# controller.net
KiCad netlist of a schematic drawn in EAGLE
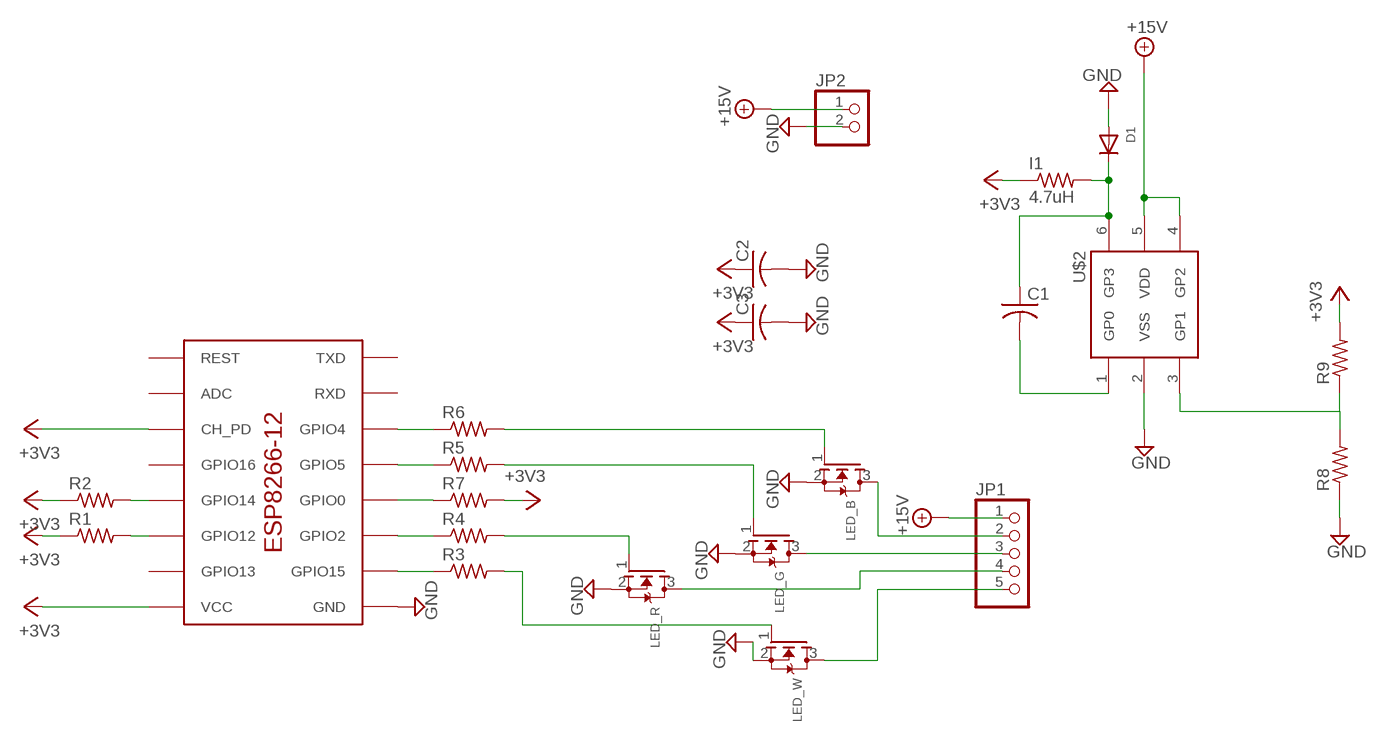
[diagram p0: schematic, sheet 1]

(export (version "E")
  (design (tool "Eeschema 10.0.6"))
  (components
    (comp (ref "C1")
      (value "C-USC0805")
      (footprint "eagle-import:C0805")
      (libsource (lib "eagle-import") (part "C-USC0805"))
    )
    (comp (ref "C2")
      (value "C-USC0805")
      (footprint "eagle-import:C0805")
      (libsource (lib "eagle-import") (part "C-USC0805"))
    )
    (comp (ref "C3")
      (value "C-USC0805")
      (footprint "eagle-import:C0805")
      (libsource (lib "eagle-import") (part "C-USC0805"))
    )
    (comp (ref "D1")
      (value "DIODESOT23_REFLOW")
      (footprint "eagle-import:SOT23-R")
      (libsource (lib "eagle-import") (part "DIODESOT23_REFLOW"))
    )
    (comp (ref "I1")
      (value "4.7uH")
      (footprint "eagle-import:R0805")
      (libsource (lib "eagle-import") (part "R-US_R0805"))
    )
    (comp (ref "JP1")
      (value "PINHD-1X5")
      (footprint "eagle-import:1X05")
      (libsource (lib "eagle-import") (part "PINHD-1X5"))
    )
    (comp (ref "JP2")
      (value "PINHD-1X2")
      (footprint "eagle-import:1X02")
      (libsource (lib "eagle-import") (part "PINHD-1X2"))
    )
    (comp (ref "LED_B")
      (value "MOSFET-NREFLOW")
      (footprint "eagle-import:SOT23")
      (libsource (lib "eagle-import") (part "MOSFET-NREFLOW"))
    )
    (comp (ref "LED_G")
      (value "MOSFET-NREFLOW")
      (footprint "eagle-import:SOT23")
      (libsource (lib "eagle-import") (part "MOSFET-NREFLOW"))
    )
    (comp (ref "LED_R")
      (value "MOSFET-NREFLOW")
      (footprint "eagle-import:SOT23")
      (libsource (lib "eagle-import") (part "MOSFET-NREFLOW"))
    )
    (comp (ref "LED_W")
      (value "MOSFET-NREFLOW")
      (footprint "eagle-import:SOT23")
      (libsource (lib "eagle-import") (part "MOSFET-NREFLOW"))
    )
    (comp (ref "R1")
      (value "R-US_R0805")
      (footprint "eagle-import:R0805")
      (libsource (lib "eagle-import") (part "R-US_R0805"))
    )
    (comp (ref "R2")
      (value "R-US_R0805")
      (footprint "eagle-import:R0805")
      (libsource (lib "eagle-import") (part "R-US_R0805"))
    )
    (comp (ref "R3")
      (value "R-US_R0805")
      (footprint "eagle-import:R0805")
      (libsource (lib "eagle-import") (part "R-US_R0805"))
    )
    (comp (ref "R4")
      (value "R-US_R0805")
      (footprint "eagle-import:R0805")
      (libsource (lib "eagle-import") (part "R-US_R0805"))
    )
    (comp (ref "R5")
      (value "R-US_R0805")
      (footprint "eagle-import:R0805")
      (libsource (lib "eagle-import") (part "R-US_R0805"))
    )
    (comp (ref "R6")
      (value "R-US_R0805")
      (footprint "eagle-import:R0805")
      (libsource (lib "eagle-import") (part "R-US_R0805"))
    )
    (comp (ref "R7")
      (value "R-US_R0805")
      (footprint "eagle-import:R0805")
      (libsource (lib "eagle-import") (part "R-US_R0805"))
    )
    (comp (ref "R8")
      (value "R-US_R0805")
      (footprint "eagle-import:R0805")
      (libsource (lib "eagle-import") (part "R-US_R0805"))
    )
    (comp (ref "R9")
      (value "R-US_R0805")
      (footprint "eagle-import:R0805")
      (libsource (lib "eagle-import") (part "R-US_R0805"))
    )
    (comp (ref "U$1")
      (value "ESP8266-12")
      (footprint "eagle-import:ESP8266-12")
      (libsource (lib "eagle-import") (part "ESP8266-12"))
    )
    (comp (ref "U$2")
      (value "10F200T")
      (footprint "eagle-import:SOT23-6")
      (libsource (lib "eagle-import") (part "10F200T"))
    )
  )
  (nets
    (net (code "1") (name "+3V3") (class "Default")
      (node (ref "C2") (pin "1") (pinfunction "1_1") (pintype "passive"))
      (node (ref "C3") (pin "1") (pinfunction "1_1") (pintype "passive"))
      (node (ref "I1") (pin "1") (pinfunction "1_1") (pintype "passive"))
      (node (ref "R1") (pin "1") (pinfunction "1_1") (pintype "passive"))
      (node (ref "R2") (pin "1") (pinfunction "1_1") (pintype "passive"))
      (node (ref "R7") (pin "2") (pinfunction "2_2") (pintype "passive"))
      (node (ref "R9") (pin "2") (pinfunction "2_2") (pintype "passive"))
      (node (ref "U$1") (pin "CH_PD") (pinfunction "CH_PD_CH_PD") (pintype "power_in"))
      (node (ref "U$1") (pin "VCC") (pinfunction "VCC_VCC") (pintype "power_in"))
    )
    (net (code "2") (name "+15V") (class "Default")
      (node (ref "JP1") (pin "1") (pinfunction "1_1") (pintype "passive"))
      (node (ref "JP2") (pin "1") (pinfunction "1_1") (pintype "passive"))
      (node (ref "U$2") (pin "4") (pinfunction "GP2_4") (pintype "bidirectional"))
      (node (ref "U$2") (pin "5") (pinfunction "VDD_5") (pintype "power_in"))
    )
    (net (code "3") (name "/ADC") (class "Default")
      (node (ref "U$1") (pin "ADC") (pinfunction "ADC_ADC") (pintype "power_in"))
    )
    (net (code "4") (name "/GPIO13") (class "Default")
      (node (ref "U$1") (pin "GPIO13") (pinfunction "GPIO13_GPIO13") (pintype "power_in"))
    )
    (net (code "5") (name "/GPIO16") (class "Default")
      (node (ref "U$1") (pin "GPIO16") (pinfunction "GPIO16_GPIO16") (pintype "power_in"))
    )
    (net (code "6") (name "/REST") (class "Default")
      (node (ref "U$1") (pin "REST") (pinfunction "REST_REST") (pintype "power_in"))
    )
    (net (code "7") (name "/RXD") (class "Default")
      (node (ref "U$1") (pin "RXD") (pinfunction "RXD_RXD") (pintype "power_in"))
    )
    (net (code "8") (name "/TXD") (class "Default")
      (node (ref "U$1") (pin "TXD") (pinfunction "TXD_TXD") (pintype "power_in"))
    )
    (net (code "9") (name "GND") (class "Default")
      (node (ref "C2") (pin "2") (pinfunction "2_2") (pintype "passive"))
      (node (ref "C3") (pin "2") (pinfunction "2_2") (pintype "passive"))
      (node (ref "D1") (pin "1") (pinfunction "A_1") (pintype "passive"))
      (node (ref "JP2") (pin "2") (pinfunction "2_2") (pintype "passive"))
      (node (ref "LED_B") (pin "2") (pinfunction "S_2") (pintype "bidirectional"))
      (node (ref "LED_G") (pin "2") (pinfunction "S_2") (pintype "bidirectional"))
      (node (ref "LED_R") (pin "2") (pinfunction "S_2") (pintype "bidirectional"))
      (node (ref "LED_W") (pin "2") (pinfunction "S_2") (pintype "bidirectional"))
      (node (ref "R8") (pin "1") (pinfunction "1_1") (pintype "passive"))
      (node (ref "U$1") (pin "GND") (pinfunction "GND_GND") (pintype "power_in"))
      (node (ref "U$2") (pin "2") (pinfunction "VSS_2") (pintype "power_in"))
    )
    (net (code "10") (name "Net-(D1-C)") (class "Default")
      (node (ref "C1") (pin "1") (pinfunction "1_1") (pintype "passive"))
      (node (ref "D1") (pin "3") (pinfunction "C_3") (pintype "passive"))
      (node (ref "I1") (pin "2") (pinfunction "2_2") (pintype "passive"))
      (node (ref "U$2") (pin "6") (pinfunction "GP3_6") (pintype "bidirectional"))
    )
    (net (code "11") (name "Net-(LED_B-D)") (class "Default")
      (node (ref "JP1") (pin "2") (pinfunction "2_2") (pintype "passive"))
      (node (ref "LED_B") (pin "3") (pinfunction "D_3") (pintype "bidirectional"))
    )
    (net (code "12") (name "Net-(LED_B-G)") (class "Default")
      (node (ref "LED_B") (pin "1") (pinfunction "G_1") (pintype "bidirectional"))
      (node (ref "R6") (pin "2") (pinfunction "2_2") (pintype "passive"))
    )
    (net (code "13") (name "Net-(LED_G-D)") (class "Default")
      (node (ref "JP1") (pin "3") (pinfunction "3_3") (pintype "passive"))
      (node (ref "LED_G") (pin "3") (pinfunction "D_3") (pintype "bidirectional"))
    )
    (net (code "14") (name "Net-(LED_G-G)") (class "Default")
      (node (ref "LED_G") (pin "1") (pinfunction "G_1") (pintype "bidirectional"))
      (node (ref "R5") (pin "2") (pinfunction "2_2") (pintype "passive"))
    )
    (net (code "15") (name "Net-(LED_R-D)") (class "Default")
      (node (ref "JP1") (pin "4") (pinfunction "4_4") (pintype "passive"))
      (node (ref "LED_R") (pin "3") (pinfunction "D_3") (pintype "bidirectional"))
    )
    (net (code "16") (name "Net-(LED_R-G)") (class "Default")
      (node (ref "LED_R") (pin "1") (pinfunction "G_1") (pintype "bidirectional"))
      (node (ref "R4") (pin "2") (pinfunction "2_2") (pintype "passive"))
    )
    (net (code "17") (name "Net-(LED_W-D)") (class "Default")
      (node (ref "JP1") (pin "5") (pinfunction "5_5") (pintype "passive"))
      (node (ref "LED_W") (pin "3") (pinfunction "D_3") (pintype "bidirectional"))
    )
    (net (code "18") (name "Net-(LED_W-G)") (class "Default")
      (node (ref "LED_W") (pin "1") (pinfunction "G_1") (pintype "bidirectional"))
      (node (ref "R3") (pin "2") (pinfunction "2_2") (pintype "passive"))
    )
    (net (code "19") (name "Net-(R1-Pad2)") (class "Default")
      (node (ref "R1") (pin "2") (pinfunction "2_2") (pintype "passive"))
      (node (ref "U$1") (pin "GPIO12") (pinfunction "GPIO12_GPIO12") (pintype "power_in"))
    )
    (net (code "20") (name "Net-(R2-Pad2)") (class "Default")
      (node (ref "R2") (pin "2") (pinfunction "2_2") (pintype "passive"))
      (node (ref "U$1") (pin "GPIO14") (pinfunction "GPIO14_GPIO14") (pintype "power_in"))
    )
    (net (code "21") (name "Net-(R3-Pad1)") (class "Default")
      (node (ref "R3") (pin "1") (pinfunction "1_1") (pintype "passive"))
      (node (ref "U$1") (pin "GPIO15") (pinfunction "GPIO15_GPIO15") (pintype "power_in"))
    )
    (net (code "22") (name "Net-(R4-Pad1)") (class "Default")
      (node (ref "R4") (pin "1") (pinfunction "1_1") (pintype "passive"))
      (node (ref "U$1") (pin "GPIO2") (pinfunction "GPIO2_GPIO2") (pintype "power_in"))
    )
    (net (code "23") (name "Net-(R5-Pad1)") (class "Default")
      (node (ref "R5") (pin "1") (pinfunction "1_1") (pintype "passive"))
      (node (ref "U$1") (pin "GPIO5") (pinfunction "GPIO5_GPIO5") (pintype "power_in"))
    )
    (net (code "24") (name "Net-(R6-Pad1)") (class "Default")
      (node (ref "R6") (pin "1") (pinfunction "1_1") (pintype "passive"))
      (node (ref "U$1") (pin "GPIO4") (pinfunction "GPIO4_GPIO4") (pintype "power_in"))
    )
    (net (code "25") (name "Net-(R7-Pad1)") (class "Default")
      (node (ref "R7") (pin "1") (pinfunction "1_1") (pintype "passive"))
      (node (ref "U$1") (pin "GPIO0") (pinfunction "GPIO0_GPIO0") (pintype "power_in"))
    )
    (net (code "26") (name "Net-(U$2-GP0)") (class "Default")
      (node (ref "C1") (pin "2") (pinfunction "2_2") (pintype "passive"))
      (node (ref "U$2") (pin "1") (pinfunction "GP0_1") (pintype "bidirectional"))
    )
    (net (code "27") (name "Net-(U$2-GP1)") (class "Default")
      (node (ref "R8") (pin "2") (pinfunction "2_2") (pintype "passive"))
      (node (ref "R9") (pin "1") (pinfunction "1_1") (pintype "passive"))
      (node (ref "U$2") (pin "3") (pinfunction "GP1_3") (pintype "bidirectional"))
    )
  )
)
